# mega_pin_out_sides.net
KiCad netlist of a schematic drawn in EAGLE
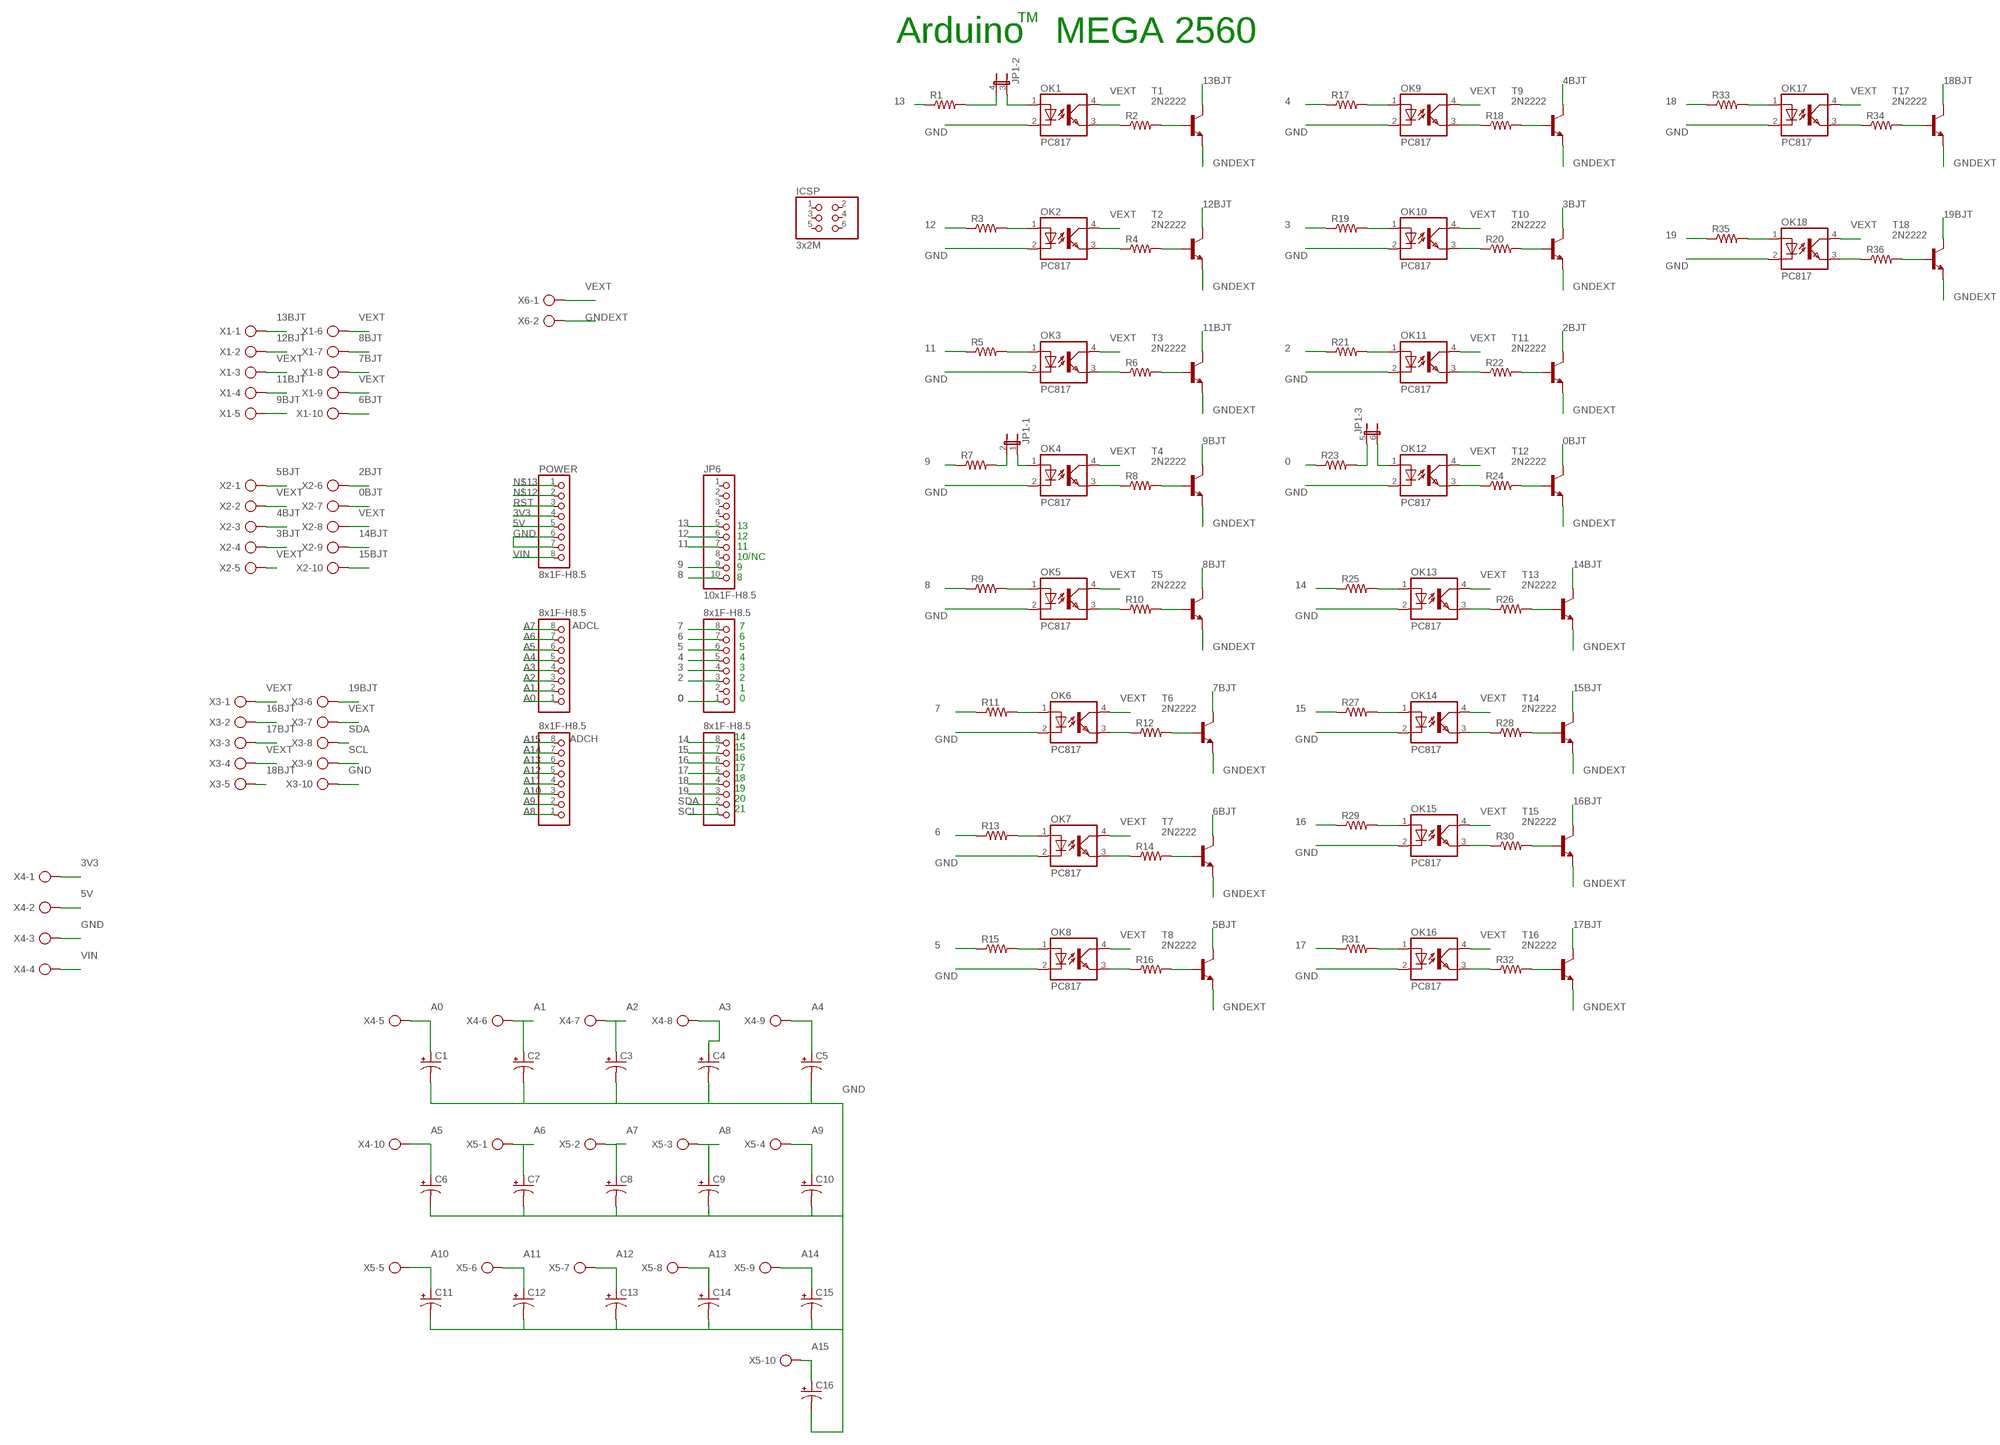
[diagram p0: schematic, sheet 1]

(export (version "E")
  (design (tool "Eeschema 10.0.6"))
  (components
    (comp (ref "ADCH")
      (value "8x1F-H8.5")
      (footprint "eagle-import:1X08")
      (libsource (lib "eagle-import") (part "PINHD-1X8"))
    )
    (comp (ref "ADCL")
      (value "8x1F-H8.5")
      (footprint "eagle-import:1X08")
      (libsource (lib "eagle-import") (part "PINHD-1X8"))
    )
    (comp (ref "C1")
      (value "CPOL-USE2-4")
      (footprint "eagle-import:E2-4")
      (libsource (lib "eagle-import") (part "CPOL-USE2-4"))
    )
    (comp (ref "C2")
      (value "CPOL-USE2-4")
      (footprint "eagle-import:E2-4")
      (libsource (lib "eagle-import") (part "CPOL-USE2-4"))
    )
    (comp (ref "C3")
      (value "CPOL-USE2-4")
      (footprint "eagle-import:E2-4")
      (libsource (lib "eagle-import") (part "CPOL-USE2-4"))
    )
    (comp (ref "C4")
      (value "CPOL-USE2-4")
      (footprint "eagle-import:E2-4")
      (libsource (lib "eagle-import") (part "CPOL-USE2-4"))
    )
    (comp (ref "C5")
      (value "CPOL-USE2-4")
      (footprint "eagle-import:E2-4")
      (libsource (lib "eagle-import") (part "CPOL-USE2-4"))
    )
    (comp (ref "C6")
      (value "CPOL-USE2-4")
      (footprint "eagle-import:E2-4")
      (libsource (lib "eagle-import") (part "CPOL-USE2-4"))
    )
    (comp (ref "C7")
      (value "CPOL-USE2-4")
      (footprint "eagle-import:E2-4")
      (libsource (lib "eagle-import") (part "CPOL-USE2-4"))
    )
    (comp (ref "C8")
      (value "CPOL-USE2-4")
      (footprint "eagle-import:E2-4")
      (libsource (lib "eagle-import") (part "CPOL-USE2-4"))
    )
    (comp (ref "C9")
      (value "CPOL-USE2-4")
      (footprint "eagle-import:E2-4")
      (libsource (lib "eagle-import") (part "CPOL-USE2-4"))
    )
    (comp (ref "C10")
      (value "CPOL-USE2-4")
      (footprint "eagle-import:E2-4")
      (libsource (lib "eagle-import") (part "CPOL-USE2-4"))
    )
    (comp (ref "C11")
      (value "CPOL-USE2-4")
      (footprint "eagle-import:E2-4")
      (libsource (lib "eagle-import") (part "CPOL-USE2-4"))
    )
    (comp (ref "C12")
      (value "CPOL-USE2-4")
      (footprint "eagle-import:E2-4")
      (libsource (lib "eagle-import") (part "CPOL-USE2-4"))
    )
    (comp (ref "C13")
      (value "CPOL-USE2-4")
      (footprint "eagle-import:E2-4")
      (libsource (lib "eagle-import") (part "CPOL-USE2-4"))
    )
    (comp (ref "C14")
      (value "CPOL-USE2-4")
      (footprint "eagle-import:E2-4")
      (libsource (lib "eagle-import") (part "CPOL-USE2-4"))
    )
    (comp (ref "C15")
      (value "CPOL-USE2-4")
      (footprint "eagle-import:E2-4")
      (libsource (lib "eagle-import") (part "CPOL-USE2-4"))
    )
    (comp (ref "C16")
      (value "CPOL-USE2-4")
      (footprint "eagle-import:E2-4")
      (libsource (lib "eagle-import") (part "CPOL-USE2-4"))
    )
    (comp (ref "COMMUNICATION")
      (value "8x1F-H8.5")
      (footprint "eagle-import:1X08")
      (libsource (lib "eagle-import") (part "PINHD-1X8"))
    )
    (comp (ref "ICSP")
      (value "3x2M")
      (footprint "eagle-import:2X03")
      (libsource (lib "eagle-import") (part "PINHD-2X3"))
    )
    (comp (ref "JP1")
      (value "JP3QE")
      (footprint "eagle-import:JP3Q")
      (libsource (lib "eagle-import") (part "JP3QE"))
    )
    (comp (ref "JP6")
      (value "10x1F-H8.5")
      (footprint "eagle-import:1X10")
      (libsource (lib "eagle-import") (part "PINHD-1X10_ARD"))
    )
    (comp (ref "OK1")
      (value "PC817")
      (footprint "eagle-import:DIL04")
      (fields (field (name "MPN") "PC817X4J000F"))
      (libsource (lib "eagle-import") (part "PC817"))
    )
    (comp (ref "OK2")
      (value "PC817")
      (footprint "eagle-import:DIL04")
      (fields (field (name "MPN") "PC817X4J000F"))
      (libsource (lib "eagle-import") (part "PC817"))
    )
    (comp (ref "OK3")
      (value "PC817")
      (footprint "eagle-import:DIL04")
      (fields (field (name "MPN") "PC817X4J000F"))
      (libsource (lib "eagle-import") (part "PC817"))
    )
    (comp (ref "OK4")
      (value "PC817")
      (footprint "eagle-import:DIL04")
      (fields (field (name "MPN") "PC817X4J000F"))
      (libsource (lib "eagle-import") (part "PC817"))
    )
    (comp (ref "OK5")
      (value "PC817")
      (footprint "eagle-import:DIL04")
      (fields (field (name "MPN") "PC817X4J000F"))
      (libsource (lib "eagle-import") (part "PC817"))
    )
    (comp (ref "OK6")
      (value "PC817")
      (footprint "eagle-import:DIL04")
      (fields (field (name "MPN") "PC817X4J000F"))
      (libsource (lib "eagle-import") (part "PC817"))
    )
    (comp (ref "OK7")
      (value "PC817")
      (footprint "eagle-import:DIL04")
      (fields (field (name "MPN") "PC817X4J000F"))
      (libsource (lib "eagle-import") (part "PC817"))
    )
    (comp (ref "OK8")
      (value "PC817")
      (footprint "eagle-import:DIL04")
      (fields (field (name "MPN") "PC817X4J000F"))
      (libsource (lib "eagle-import") (part "PC817"))
    )
    (comp (ref "OK9")
      (value "PC817")
      (footprint "eagle-import:DIL04")
      (fields (field (name "MPN") "PC817X4J000F"))
      (libsource (lib "eagle-import") (part "PC817"))
    )
    (comp (ref "OK10")
      (value "PC817")
      (footprint "eagle-import:DIL04")
      (fields (field (name "MPN") "PC817X4J000F"))
      (libsource (lib "eagle-import") (part "PC817"))
    )
    (comp (ref "OK11")
      (value "PC817")
      (footprint "eagle-import:DIL04")
      (fields (field (name "MPN") "PC817X4J000F"))
      (libsource (lib "eagle-import") (part "PC817"))
    )
    (comp (ref "OK12")
      (value "PC817")
      (footprint "eagle-import:DIL04")
      (fields (field (name "MPN") "PC817X4J000F"))
      (libsource (lib "eagle-import") (part "PC817"))
    )
    (comp (ref "OK13")
      (value "PC817")
      (footprint "eagle-import:DIL04")
      (fields (field (name "MPN") "PC817X4J000F"))
      (libsource (lib "eagle-import") (part "PC817"))
    )
    (comp (ref "OK14")
      (value "PC817")
      (footprint "eagle-import:DIL04")
      (fields (field (name "MPN") "PC817X4J000F"))
      (libsource (lib "eagle-import") (part "PC817"))
    )
    (comp (ref "OK15")
      (value "PC817")
      (footprint "eagle-import:DIL04")
      (fields (field (name "MPN") "PC817X4J000F"))
      (libsource (lib "eagle-import") (part "PC817"))
    )
    (comp (ref "OK16")
      (value "PC817")
      (footprint "eagle-import:DIL04")
      (fields (field (name "MPN") "PC817X4J000F"))
      (libsource (lib "eagle-import") (part "PC817"))
    )
    (comp (ref "OK17")
      (value "PC817")
      (footprint "eagle-import:DIL04")
      (fields (field (name "MPN") "PC817X4J000F"))
      (libsource (lib "eagle-import") (part "PC817"))
    )
    (comp (ref "OK18")
      (value "PC817")
      (footprint "eagle-import:DIL04")
      (fields (field (name "MPN") "PC817X4J000F"))
      (libsource (lib "eagle-import") (part "PC817"))
    )
    (comp (ref "POWER")
      (value "8x1F-H8.5")
      (footprint "eagle-import:1X08")
      (libsource (lib "eagle-import") (part "PINHD-1X8"))
    )
    (comp (ref "PWML")
      (value "8x1F-H8.5")
      (footprint "eagle-import:1X08")
      (libsource (lib "eagle-import") (part "PINHD-1X8"))
    )
    (comp (ref "R1")
      (value "R-US_M1206")
      (footprint "eagle-import:M1206")
      (libsource (lib "eagle-import") (part "R-US_M1206"))
    )
    (comp (ref "R2")
      (value "R-US_M1206")
      (footprint "eagle-import:M1206")
      (libsource (lib "eagle-import") (part "R-US_M1206"))
    )
    (comp (ref "R3")
      (value "R-US_M1206")
      (footprint "eagle-import:M1206")
      (libsource (lib "eagle-import") (part "R-US_M1206"))
    )
    (comp (ref "R4")
      (value "R-US_M1206")
      (footprint "eagle-import:M1206")
      (libsource (lib "eagle-import") (part "R-US_M1206"))
    )
    (comp (ref "R5")
      (value "R-US_M1206")
      (footprint "eagle-import:M1206")
      (libsource (lib "eagle-import") (part "R-US_M1206"))
    )
    (comp (ref "R6")
      (value "R-US_M1206")
      (footprint "eagle-import:M1206")
      (libsource (lib "eagle-import") (part "R-US_M1206"))
    )
    (comp (ref "R7")
      (value "R-US_M1206")
      (footprint "eagle-import:M1206")
      (libsource (lib "eagle-import") (part "R-US_M1206"))
    )
    (comp (ref "R8")
      (value "R-US_M1206")
      (footprint "eagle-import:M1206")
      (libsource (lib "eagle-import") (part "R-US_M1206"))
    )
    (comp (ref "R9")
      (value "R-US_M1206")
      (footprint "eagle-import:M1206")
      (libsource (lib "eagle-import") (part "R-US_M1206"))
    )
    (comp (ref "R10")
      (value "R-US_M1206")
      (footprint "eagle-import:M1206")
      (libsource (lib "eagle-import") (part "R-US_M1206"))
    )
    (comp (ref "R11")
      (value "R-US_M1206")
      (footprint "eagle-import:M1206")
      (libsource (lib "eagle-import") (part "R-US_M1206"))
    )
    (comp (ref "R12")
      (value "R-US_M1206")
      (footprint "eagle-import:M1206")
      (libsource (lib "eagle-import") (part "R-US_M1206"))
    )
    (comp (ref "R13")
      (value "R-US_M1206")
      (footprint "eagle-import:M1206")
      (libsource (lib "eagle-import") (part "R-US_M1206"))
    )
    (comp (ref "R14")
      (value "R-US_M1206")
      (footprint "eagle-import:M1206")
      (libsource (lib "eagle-import") (part "R-US_M1206"))
    )
    (comp (ref "R15")
      (value "R-US_M1206")
      (footprint "eagle-import:M1206")
      (libsource (lib "eagle-import") (part "R-US_M1206"))
    )
    (comp (ref "R16")
      (value "R-US_M1206")
      (footprint "eagle-import:M1206")
      (libsource (lib "eagle-import") (part "R-US_M1206"))
    )
    (comp (ref "R17")
      (value "R-US_M1206")
      (footprint "eagle-import:M1206")
      (libsource (lib "eagle-import") (part "R-US_M1206"))
    )
    (comp (ref "R18")
      (value "R-US_M1206")
      (footprint "eagle-import:M1206")
      (libsource (lib "eagle-import") (part "R-US_M1206"))
    )
    (comp (ref "R19")
      (value "R-US_M1206")
      (footprint "eagle-import:M1206")
      (libsource (lib "eagle-import") (part "R-US_M1206"))
    )
    (comp (ref "R20")
      (value "R-US_M1206")
      (footprint "eagle-import:M1206")
      (libsource (lib "eagle-import") (part "R-US_M1206"))
    )
    (comp (ref "R21")
      (value "R-US_M1206")
      (footprint "eagle-import:M1206")
      (libsource (lib "eagle-import") (part "R-US_M1206"))
    )
    (comp (ref "R22")
      (value "R-US_M1206")
      (footprint "eagle-import:M1206")
      (libsource (lib "eagle-import") (part "R-US_M1206"))
    )
    (comp (ref "R23")
      (value "R-US_M1206")
      (footprint "eagle-import:M1206")
      (libsource (lib "eagle-import") (part "R-US_M1206"))
    )
    (comp (ref "R24")
      (value "R-US_M1206")
      (footprint "eagle-import:M1206")
      (libsource (lib "eagle-import") (part "R-US_M1206"))
    )
    (comp (ref "R25")
      (value "R-US_M1206")
      (footprint "eagle-import:M1206")
      (libsource (lib "eagle-import") (part "R-US_M1206"))
    )
    (comp (ref "R26")
      (value "R-US_M1206")
      (footprint "eagle-import:M1206")
      (libsource (lib "eagle-import") (part "R-US_M1206"))
    )
    (comp (ref "R27")
      (value "R-US_M1206")
      (footprint "eagle-import:M1206")
      (libsource (lib "eagle-import") (part "R-US_M1206"))
    )
    (comp (ref "R28")
      (value "R-US_M1206")
      (footprint "eagle-import:M1206")
      (libsource (lib "eagle-import") (part "R-US_M1206"))
    )
    (comp (ref "R29")
      (value "R-US_M1206")
      (footprint "eagle-import:M1206")
      (libsource (lib "eagle-import") (part "R-US_M1206"))
    )
    (comp (ref "R30")
      (value "R-US_M1206")
      (footprint "eagle-import:M1206")
      (libsource (lib "eagle-import") (part "R-US_M1206"))
    )
    (comp (ref "R31")
      (value "R-US_M1206")
      (footprint "eagle-import:M1206")
      (libsource (lib "eagle-import") (part "R-US_M1206"))
    )
    (comp (ref "R32")
      (value "R-US_M1206")
      (footprint "eagle-import:M1206")
      (libsource (lib "eagle-import") (part "R-US_M1206"))
    )
    (comp (ref "R33")
      (value "R-US_M1206")
      (footprint "eagle-import:M1206")
      (libsource (lib "eagle-import") (part "R-US_M1206"))
    )
    (comp (ref "R34")
      (value "R-US_M1206")
      (footprint "eagle-import:M1206")
      (libsource (lib "eagle-import") (part "R-US_M1206"))
    )
    (comp (ref "R35")
      (value "R-US_M1206")
      (footprint "eagle-import:M1206")
      (libsource (lib "eagle-import") (part "R-US_M1206"))
    )
    (comp (ref "R36")
      (value "R-US_M1206")
      (footprint "eagle-import:M1206")
      (libsource (lib "eagle-import") (part "R-US_M1206"))
    )
    (comp (ref "T1")
      (value "2N2222")
      (footprint "eagle-import:TO18")
      (libsource (lib "eagle-import") (part "2N2222"))
    )
    (comp (ref "T2")
      (value "2N2222")
      (footprint "eagle-import:TO18")
      (libsource (lib "eagle-import") (part "2N2222"))
    )
    (comp (ref "T3")
      (value "2N2222")
      (footprint "eagle-import:TO18")
      (libsource (lib "eagle-import") (part "2N2222"))
    )
    (comp (ref "T4")
      (value "2N2222")
      (footprint "eagle-import:TO18")
      (libsource (lib "eagle-import") (part "2N2222"))
    )
    (comp (ref "T5")
      (value "2N2222")
      (footprint "eagle-import:TO18")
      (libsource (lib "eagle-import") (part "2N2222"))
    )
    (comp (ref "T6")
      (value "2N2222")
      (footprint "eagle-import:TO18")
      (libsource (lib "eagle-import") (part "2N2222"))
    )
    (comp (ref "T7")
      (value "2N2222")
      (footprint "eagle-import:TO18")
      (libsource (lib "eagle-import") (part "2N2222"))
    )
    (comp (ref "T8")
      (value "2N2222")
      (footprint "eagle-import:TO18")
      (libsource (lib "eagle-import") (part "2N2222"))
    )
    (comp (ref "T9")
      (value "2N2222")
      (footprint "eagle-import:TO18")
      (libsource (lib "eagle-import") (part "2N2222"))
    )
    (comp (ref "T10")
      (value "2N2222")
      (footprint "eagle-import:TO18")
      (libsource (lib "eagle-import") (part "2N2222"))
    )
    (comp (ref "T11")
      (value "2N2222")
      (footprint "eagle-import:TO18")
      (libsource (lib "eagle-import") (part "2N2222"))
    )
    (comp (ref "T12")
      (value "2N2222")
      (footprint "eagle-import:TO18")
      (libsource (lib "eagle-import") (part "2N2222"))
    )
    (comp (ref "T13")
      (value "2N2222")
      (footprint "eagle-import:TO18")
      (libsource (lib "eagle-import") (part "2N2222"))
    )
    (comp (ref "T14")
      (value "2N2222")
      (footprint "eagle-import:TO18")
      (libsource (lib "eagle-import") (part "2N2222"))
    )
    (comp (ref "T15")
      (value "2N2222")
      (footprint "eagle-import:TO18")
      (libsource (lib "eagle-import") (part "2N2222"))
    )
    (comp (ref "T16")
      (value "2N2222")
      (footprint "eagle-import:TO18")
      (libsource (lib "eagle-import") (part "2N2222"))
    )
    (comp (ref "T17")
      (value "2N2222")
      (footprint "eagle-import:TO18")
      (libsource (lib "eagle-import") (part "2N2222"))
    )
    (comp (ref "T18")
      (value "2N2222")
      (footprint "eagle-import:TO18")
      (libsource (lib "eagle-import") (part "2N2222"))
    )
    (comp (ref "X1")
      (value "AK500/10")
      (footprint "eagle-import:AK500_10")
      (libsource (lib "eagle-import") (part "AK500/10"))
    )
    (comp (ref "X2")
      (value "AK500/10")
      (footprint "eagle-import:AK500_10")
      (libsource (lib "eagle-import") (part "AK500/10"))
    )
    (comp (ref "X3")
      (value "AK500/10")
      (footprint "eagle-import:AK500_10")
      (libsource (lib "eagle-import") (part "AK500/10"))
    )
    (comp (ref "X4")
      (value "AK500/10")
      (footprint "eagle-import:AK500_10")
      (libsource (lib "eagle-import") (part "AK500/10"))
    )
    (comp (ref "X5")
      (value "AK500/10")
      (footprint "eagle-import:AK500_10")
      (libsource (lib "eagle-import") (part "AK500/10"))
    )
    (comp (ref "X6")
      (value "AK500/2")
      (footprint "eagle-import:AK500_2")
      (libsource (lib "eagle-import") (part "AK500/2"))
    )
  )
  (nets
    (net (code "1") (name "/0") (class "Default")
      (node (ref "PWML") (pin "1") (pinfunction "1_1") (pintype "passive"))
      (node (ref "R23") (pin "1") (pinfunction "1_1") (pintype "passive"))
    )
    (net (code "2") (name "/0BJT") (class "Default")
      (node (ref "T12") (pin "3") (pinfunction "C_3") (pintype "passive"))
      (node (ref "X2") (pin "7") (pinfunction "KL_7") (pintype "passive"))
    )
    (net (code "3") (name "/2") (class "Default")
      (node (ref "PWML") (pin "3") (pinfunction "3_3") (pintype "passive"))
      (node (ref "R21") (pin "1") (pinfunction "1_1") (pintype "passive"))
    )
    (net (code "4") (name "/2BJT") (class "Default")
      (node (ref "T11") (pin "3") (pinfunction "C_3") (pintype "passive"))
      (node (ref "X2") (pin "6") (pinfunction "KL_6") (pintype "passive"))
    )
    (net (code "5") (name "/3") (class "Default")
      (node (ref "PWML") (pin "4") (pinfunction "4_4") (pintype "passive"))
      (node (ref "R19") (pin "1") (pinfunction "1_1") (pintype "passive"))
    )
    (net (code "6") (name "/3BJT") (class "Default")
      (node (ref "T10") (pin "3") (pinfunction "C_3") (pintype "passive"))
      (node (ref "X2") (pin "4") (pinfunction "KL_4") (pintype "passive"))
    )
    (net (code "7") (name "/3V3") (class "Default")
      (node (ref "POWER") (pin "4") (pinfunction "4_4") (pintype "passive"))
      (node (ref "X4") (pin "1") (pinfunction "KL_1") (pintype "passive"))
    )
    (net (code "8") (name "/4") (class "Default")
      (node (ref "PWML") (pin "5") (pinfunction "5_5") (pintype "passive"))
      (node (ref "R17") (pin "1") (pinfunction "1_1") (pintype "passive"))
    )
    (net (code "9") (name "/4BJT") (class "Default")
      (node (ref "T9") (pin "3") (pinfunction "C_3") (pintype "passive"))
      (node (ref "X2") (pin "3") (pinfunction "KL_3") (pintype "passive"))
    )
    (net (code "10") (name "/5") (class "Default")
      (node (ref "PWML") (pin "6") (pinfunction "6_6") (pintype "passive"))
      (node (ref "R15") (pin "1") (pinfunction "1_1") (pintype "passive"))
    )
    (net (code "11") (name "/5BJT") (class "Default")
      (node (ref "T8") (pin "3") (pinfunction "C_3") (pintype "passive"))
      (node (ref "X2") (pin "1") (pinfunction "KL_1") (pintype "passive"))
    )
    (net (code "12") (name "/5V") (class "Default")
      (node (ref "POWER") (pin "5") (pinfunction "5_5") (pintype "passive"))
      (node (ref "X4") (pin "2") (pinfunction "KL_2") (pintype "passive"))
    )
    (net (code "13") (name "/6") (class "Default")
      (node (ref "PWML") (pin "7") (pinfunction "7_7") (pintype "passive"))
      (node (ref "R13") (pin "1") (pinfunction "1_1") (pintype "passive"))
    )
    (net (code "14") (name "/6BJT") (class "Default")
      (node (ref "T7") (pin "3") (pinfunction "C_3") (pintype "passive"))
      (node (ref "X1") (pin "10") (pinfunction "KL_10") (pintype "passive"))
    )
    (net (code "15") (name "/7") (class "Default")
      (node (ref "PWML") (pin "8") (pinfunction "8_8") (pintype "passive"))
      (node (ref "R11") (pin "1") (pinfunction "1_1") (pintype "passive"))
    )
    (net (code "16") (name "/7BJT") (class "Default")
      (node (ref "T6") (pin "3") (pinfunction "C_3") (pintype "passive"))
      (node (ref "X1") (pin "8") (pinfunction "KL_8") (pintype "passive"))
    )
    (net (code "17") (name "/8") (class "Default")
      (node (ref "JP6") (pin "10") (pinfunction "10_10") (pintype "passive"))
      (node (ref "R9") (pin "1") (pinfunction "1_1") (pintype "passive"))
    )
    (net (code "18") (name "/8BJT") (class "Default")
      (node (ref "T5") (pin "3") (pinfunction "C_3") (pintype "passive"))
      (node (ref "X1") (pin "7") (pinfunction "KL_7") (pintype "passive"))
    )
    (net (code "19") (name "/9") (class "Default")
      (node (ref "JP6") (pin "9") (pinfunction "9_9") (pintype "passive"))
      (node (ref "R7") (pin "1") (pinfunction "1_1") (pintype "passive"))
    )
    (net (code "20") (name "/9BJT") (class "Default")
      (node (ref "T4") (pin "3") (pinfunction "C_3") (pintype "passive"))
      (node (ref "X1") (pin "5") (pinfunction "KL_5") (pintype "passive"))
    )
    (net (code "21") (name "/11") (class "Default")
      (node (ref "JP6") (pin "7") (pinfunction "7_7") (pintype "passive"))
      (node (ref "R5") (pin "1") (pinfunction "1_1") (pintype "passive"))
    )
    (net (code "22") (name "/11BJT") (class "Default")
      (node (ref "T3") (pin "3") (pinfunction "C_3") (pintype "passive"))
      (node (ref "X1") (pin "4") (pinfunction "KL_4") (pintype "passive"))
    )
    (net (code "23") (name "/12") (class "Default")
      (node (ref "JP6") (pin "6") (pinfunction "6_6") (pintype "passive"))
      (node (ref "R3") (pin "1") (pinfunction "1_1") (pintype "passive"))
    )
    (net (code "24") (name "/12BJT") (class "Default")
      (node (ref "T2") (pin "3") (pinfunction "C_3") (pintype "passive"))
      (node (ref "X1") (pin "2") (pinfunction "KL_2") (pintype "passive"))
    )
    (net (code "25") (name "/13") (class "Default")
      (node (ref "JP6") (pin "5") (pinfunction "5_5") (pintype "passive"))
      (node (ref "R1") (pin "1") (pinfunction "1_1") (pintype "passive"))
    )
    (net (code "26") (name "/13BJT") (class "Default")
      (node (ref "T1") (pin "3") (pinfunction "C_3") (pintype "passive"))
      (node (ref "X1") (pin "1") (pinfunction "KL_1") (pintype "passive"))
    )
    (net (code "27") (name "/14") (class "Default")
      (node (ref "COMMUNICATION") (pin "8") (pinfunction "8_8") (pintype "passive"))
      (node (ref "R25") (pin "1") (pinfunction "1_1") (pintype "passive"))
    )
    (net (code "28") (name "/14BJT") (class "Default")
      (node (ref "T13") (pin "3") (pinfunction "C_3") (pintype "passive"))
      (node (ref "X2") (pin "9") (pinfunction "KL_9") (pintype "passive"))
    )
    (net (code "29") (name "/15") (class "Default")
      (node (ref "COMMUNICATION") (pin "7") (pinfunction "7_7") (pintype "passive"))
      (node (ref "R27") (pin "1") (pinfunction "1_1") (pintype "passive"))
    )
    (net (code "30") (name "/15BJT") (class "Default")
      (node (ref "T14") (pin "3") (pinfunction "C_3") (pintype "passive"))
      (node (ref "X2") (pin "10") (pinfunction "KL_10") (pintype "passive"))
    )
    (net (code "31") (name "/16") (class "Default")
      (node (ref "COMMUNICATION") (pin "6") (pinfunction "6_6") (pintype "passive"))
      (node (ref "R29") (pin "1") (pinfunction "1_1") (pintype "passive"))
    )
    (net (code "32") (name "/16BJT") (class "Default")
      (node (ref "T15") (pin "3") (pinfunction "C_3") (pintype "passive"))
      (node (ref "X3") (pin "2") (pinfunction "KL_2") (pintype "passive"))
    )
    (net (code "33") (name "/17") (class "Default")
      (node (ref "COMMUNICATION") (pin "5") (pinfunction "5_5") (pintype "passive"))
      (node (ref "R31") (pin "1") (pinfunction "1_1") (pintype "passive"))
    )
    (net (code "34") (name "/17BJT") (class "Default")
      (node (ref "T16") (pin "3") (pinfunction "C_3") (pintype "passive"))
      (node (ref "X3") (pin "3") (pinfunction "KL_3") (pintype "passive"))
    )
    (net (code "35") (name "/18") (class "Default")
      (node (ref "COMMUNICATION") (pin "4") (pinfunction "4_4") (pintype "passive"))
      (node (ref "R33") (pin "1") (pinfunction "1_1") (pintype "passive"))
    )
    (net (code "36") (name "/18BJT") (class "Default")
      (node (ref "T17") (pin "3") (pinfunction "C_3") (pintype "passive"))
      (node (ref "X3") (pin "5") (pinfunction "KL_5") (pintype "passive"))
    )
    (net (code "37") (name "/19") (class "Default")
      (node (ref "COMMUNICATION") (pin "3") (pinfunction "3_3") (pintype "passive"))
      (node (ref "R35") (pin "1") (pinfunction "1_1") (pintype "passive"))
    )
    (net (code "38") (name "/19BJT") (class "Default")
      (node (ref "T18") (pin "3") (pinfunction "C_3") (pintype "passive"))
      (node (ref "X3") (pin "6") (pinfunction "KL_6") (pintype "passive"))
    )
    (net (code "39") (name "/A0") (class "Default")
      (node (ref "ADCL") (pin "1") (pinfunction "1_1") (pintype "passive"))
      (node (ref "C1") (pin "+") (pinfunction "+_+") (pintype "passive"))
      (node (ref "X4") (pin "5") (pinfunction "KL_5") (pintype "passive"))
    )
    (net (code "40") (name "/A1") (class "Default")
      (node (ref "ADCL") (pin "2") (pinfunction "2_2") (pintype "passive"))
      (node (ref "C2") (pin "+") (pinfunction "+_+") (pintype "passive"))
      (node (ref "X4") (pin "6") (pinfunction "KL_6") (pintype "passive"))
    )
    (net (code "41") (name "/A2") (class "Default")
      (node (ref "ADCL") (pin "3") (pinfunction "3_3") (pintype "passive"))
      (node (ref "C3") (pin "+") (pinfunction "+_+") (pintype "passive"))
      (node (ref "X4") (pin "7") (pinfunction "KL_7") (pintype "passive"))
    )
    (net (code "42") (name "/A3") (class "Default")
      (node (ref "ADCL") (pin "4") (pinfunction "4_4") (pintype "passive"))
      (node (ref "C4") (pin "+") (pinfunction "+_+") (pintype "passive"))
      (node (ref "X4") (pin "8") (pinfunction "KL_8") (pintype "passive"))
    )
    (net (code "43") (name "/A4") (class "Default")
      (node (ref "ADCL") (pin "5") (pinfunction "5_5") (pintype "passive"))
      (node (ref "C5") (pin "+") (pinfunction "+_+") (pintype "passive"))
      (node (ref "X4") (pin "9") (pinfunction "KL_9") (pintype "passive"))
    )
    (net (code "44") (name "/A5") (class "Default")
      (node (ref "ADCL") (pin "6") (pinfunction "6_6") (pintype "passive"))
      (node (ref "C6") (pin "+") (pinfunction "+_+") (pintype "passive"))
      (node (ref "X4") (pin "10") (pinfunction "KL_10") (pintype "passive"))
    )
    (net (code "45") (name "/A6") (class "Default")
      (node (ref "ADCL") (pin "7") (pinfunction "7_7") (pintype "passive"))
      (node (ref "C7") (pin "+") (pinfunction "+_+") (pintype "passive"))
      (node (ref "X5") (pin "1") (pinfunction "KL_1") (pintype "passive"))
    )
    (net (code "46") (name "/A7") (class "Default")
      (node (ref "ADCL") (pin "8") (pinfunction "8_8") (pintype "passive"))
      (node (ref "C8") (pin "+") (pinfunction "+_+") (pintype "passive"))
      (node (ref "X5") (pin "2") (pinfunction "KL_2") (pintype "passive"))
    )
    (net (code "47") (name "/A8") (class "Default")
      (node (ref "ADCH") (pin "1") (pinfunction "1_1") (pintype "passive"))
      (node (ref "C9") (pin "+") (pinfunction "+_+") (pintype "passive"))
      (node (ref "X5") (pin "3") (pinfunction "KL_3") (pintype "passive"))
    )
    (net (code "48") (name "/A9") (class "Default")
      (node (ref "ADCH") (pin "2") (pinfunction "2_2") (pintype "passive"))
      (node (ref "C10") (pin "+") (pinfunction "+_+") (pintype "passive"))
      (node (ref "X5") (pin "4") (pinfunction "KL_4") (pintype "passive"))
    )
    (net (code "49") (name "/A10") (class "Default")
      (node (ref "ADCH") (pin "3") (pinfunction "3_3") (pintype "passive"))
      (node (ref "C11") (pin "+") (pinfunction "+_+") (pintype "passive"))
      (node (ref "X5") (pin "5") (pinfunction "KL_5") (pintype "passive"))
    )
    (net (code "50") (name "/A11") (class "Default")
      (node (ref "ADCH") (pin "4") (pinfunction "4_4") (pintype "passive"))
      (node (ref "C12") (pin "+") (pinfunction "+_+") (pintype "passive"))
      (node (ref "X5") (pin "6") (pinfunction "KL_6") (pintype "passive"))
    )
    (net (code "51") (name "/A12") (class "Default")
      (node (ref "ADCH") (pin "5") (pinfunction "5_5") (pintype "passive"))
      (node (ref "C13") (pin "+") (pinfunction "+_+") (pintype "passive"))
      (node (ref "X5") (pin "7") (pinfunction "KL_7") (pintype "passive"))
    )
    (net (code "52") (name "/A13") (class "Default")
      (node (ref "ADCH") (pin "6") (pinfunction "6_6") (pintype "passive"))
      (node (ref "C14") (pin "+") (pinfunction "+_+") (pintype "passive"))
      (node (ref "X5") (pin "8") (pinfunction "KL_8") (pintype "passive"))
    )
    (net (code "53") (name "/A14") (class "Default")
      (node (ref "ADCH") (pin "7") (pinfunction "7_7") (pintype "passive"))
      (node (ref "C15") (pin "+") (pinfunction "+_+") (pintype "passive"))
      (node (ref "X5") (pin "9") (pinfunction "KL_9") (pintype "passive"))
    )
    (net (code "54") (name "/A15") (class "Default")
      (node (ref "ADCH") (pin "8") (pinfunction "8_8") (pintype "passive"))
      (node (ref "C16") (pin "+") (pinfunction "+_+") (pintype "passive"))
      (node (ref "X5") (pin "10") (pinfunction "KL_10") (pintype "passive"))
    )
    (net (code "55") (name "/GND") (class "Default")
      (node (ref "C1") (pin "-") (pinfunction "-_-") (pintype "passive"))
      (node (ref "C10") (pin "-") (pinfunction "-_-") (pintype "passive"))
      (node (ref "C11") (pin "-") (pinfunction "-_-") (pintype "passive"))
      (node (ref "C12") (pin "-") (pinfunction "-_-") (pintype "passive"))
      (node (ref "C13") (pin "-") (pinfunction "-_-") (pintype "passive"))
      (node (ref "C14") (pin "-") (pinfunction "-_-") (pintype "passive"))
      (node (ref "C15") (pin "-") (pinfunction "-_-") (pintype "passive"))
      (node (ref "C16") (pin "-") (pinfunction "-_-") (pintype "passive"))
      (node (ref "C2") (pin "-") (pinfunction "-_-") (pintype "passive"))
      (node (ref "C3") (pin "-") (pinfunction "-_-") (pintype "passive"))
      (node (ref "C4") (pin "-") (pinfunction "-_-") (pintype "passive"))
      (node (ref "C5") (pin "-") (pinfunction "-_-") (pintype "passive"))
      (node (ref "C6") (pin "-") (pinfunction "-_-") (pintype "passive"))
      (node (ref "C7") (pin "-") (pinfunction "-_-") (pintype "passive"))
      (node (ref "C8") (pin "-") (pinfunction "-_-") (pintype "passive"))
      (node (ref "C9") (pin "-") (pinfunction "-_-") (pintype "passive"))
      (node (ref "OK1") (pin "2") (pinfunction "C_2") (pintype "passive"))
      (node (ref "OK10") (pin "2") (pinfunction "C_2") (pintype "passive"))
      (node (ref "OK11") (pin "2") (pinfunction "C_2") (pintype "passive"))
      (node (ref "OK12") (pin "2") (pinfunction "C_2") (pintype "passive"))
      (node (ref "OK13") (pin "2") (pinfunction "C_2") (pintype "passive"))
      (node (ref "OK14") (pin "2") (pinfunction "C_2") (pintype "passive"))
      (node (ref "OK15") (pin "2") (pinfunction "C_2") (pintype "passive"))
      (node (ref "OK16") (pin "2") (pinfunction "C_2") (pintype "passive"))
      (node (ref "OK17") (pin "2") (pinfunction "C_2") (pintype "passive"))
      (node (ref "OK18") (pin "2") (pinfunction "C_2") (pintype "passive"))
      (node (ref "OK2") (pin "2") (pinfunction "C_2") (pintype "passive"))
      (node (ref "OK3") (pin "2") (pinfunction "C_2") (pintype "passive"))
      (node (ref "OK4") (pin "2") (pinfunction "C_2") (pintype "passive"))
      (node (ref "OK5") (pin "2") (pinfunction "C_2") (pintype "passive"))
      (node (ref "OK6") (pin "2") (pinfunction "C_2") (pintype "passive"))
      (node (ref "OK7") (pin "2") (pinfunction "C_2") (pintype "passive"))
      (node (ref "OK8") (pin "2") (pinfunction "C_2") (pintype "passive"))
      (node (ref "OK9") (pin "2") (pinfunction "C_2") (pintype "passive"))
      (node (ref "POWER") (pin "6") (pinfunction "6_6") (pintype "passive"))
      (node (ref "POWER") (pin "7") (pinfunction "7_7") (pintype "passive"))
      (node (ref "X3") (pin "10") (pinfunction "KL_10") (pintype "passive"))
      (node (ref "X4") (pin "3") (pinfunction "KL_3") (pintype "passive"))
    )
    (net (code "56") (name "/GNDEXT") (class "Default")
      (node (ref "T1") (pin "1") (pinfunction "E_1") (pintype "passive"))
      (node (ref "T10") (pin "1") (pinfunction "E_1") (pintype "passive"))
      (node (ref "T11") (pin "1") (pinfunction "E_1") (pintype "passive"))
      (node (ref "T12") (pin "1") (pinfunction "E_1") (pintype "passive"))
      (node (ref "T13") (pin "1") (pinfunction "E_1") (pintype "passive"))
      (node (ref "T14") (pin "1") (pinfunction "E_1") (pintype "passive"))
      (node (ref "T15") (pin "1") (pinfunction "E_1") (pintype "passive"))
      (node (ref "T16") (pin "1") (pinfunction "E_1") (pintype "passive"))
      (node (ref "T17") (pin "1") (pinfunction "E_1") (pintype "passive"))
      (node (ref "T18") (pin "1") (pinfunction "E_1") (pintype "passive"))
      (node (ref "T2") (pin "1") (pinfunction "E_1") (pintype "passive"))
      (node (ref "T3") (pin "1") (pinfunction "E_1") (pintype "passive"))
      (node (ref "T4") (pin "1") (pinfunction "E_1") (pintype "passive"))
      (node (ref "T5") (pin "1") (pinfunction "E_1") (pintype "passive"))
      (node (ref "T6") (pin "1") (pinfunction "E_1") (pintype "passive"))
      (node (ref "T7") (pin "1") (pinfunction "E_1") (pintype "passive"))
      (node (ref "T8") (pin "1") (pinfunction "E_1") (pintype "passive"))
      (node (ref "T9") (pin "1") (pinfunction "E_1") (pintype "passive"))
      (node (ref "X6") (pin "2") (pinfunction "KL_2") (pintype "passive"))
    )
    (net (code "57") (name "/N$12") (class "Default")
      (node (ref "POWER") (pin "2") (pinfunction "2_2") (pintype "passive"))
    )
    (net (code "58") (name "/N$13") (class "Default")
      (node (ref "POWER") (pin "1") (pinfunction "1_1") (pintype "passive"))
    )
    (net (code "59") (name "/RST") (class "Default")
      (node (ref "POWER") (pin "3") (pinfunction "3_3") (pintype "passive"))
    )
    (net (code "60") (name "/SCL") (class "Default")
      (node (ref "COMMUNICATION") (pin "1") (pinfunction "1_1") (pintype "passive"))
      (node (ref "X3") (pin "9") (pinfunction "KL_9") (pintype "passive"))
    )
    (net (code "61") (name "/SDA") (class "Default")
      (node (ref "COMMUNICATION") (pin "2") (pinfunction "2_2") (pintype "passive"))
      (node (ref "X3") (pin "8") (pinfunction "KL_8") (pintype "passive"))
    )
    (net (code "62") (name "/VEXT") (class "Default")
      (node (ref "OK1") (pin "4") (pinfunction "COL_4") (pintype "passive"))
      (node (ref "OK10") (pin "4") (pinfunction "COL_4") (pintype "passive"))
      (node (ref "OK11") (pin "4") (pinfunction "COL_4") (pintype "passive"))
      (node (ref "OK12") (pin "4") (pinfunction "COL_4") (pintype "passive"))
      (node (ref "OK13") (pin "4") (pinfunction "COL_4") (pintype "passive"))
      (node (ref "OK14") (pin "4") (pinfunction "COL_4") (pintype "passive"))
      (node (ref "OK15") (pin "4") (pinfunction "COL_4") (pintype "passive"))
      (node (ref "OK16") (pin "4") (pinfunction "COL_4") (pintype "passive"))
      (node (ref "OK17") (pin "4") (pinfunction "COL_4") (pintype "passive"))
      (node (ref "OK18") (pin "4") (pinfunction "COL_4") (pintype "passive"))
      (node (ref "OK2") (pin "4") (pinfunction "COL_4") (pintype "passive"))
      (node (ref "OK3") (pin "4") (pinfunction "COL_4") (pintype "passive"))
      (node (ref "OK4") (pin "4") (pinfunction "COL_4") (pintype "passive"))
      (node (ref "OK5") (pin "4") (pinfunction "COL_4") (pintype "passive"))
      (node (ref "OK6") (pin "4") (pinfunction "COL_4") (pintype "passive"))
      (node (ref "OK7") (pin "4") (pinfunction "COL_4") (pintype "passive"))
      (node (ref "OK8") (pin "4") (pinfunction "COL_4") (pintype "passive"))
      (node (ref "OK9") (pin "4") (pinfunction "COL_4") (pintype "passive"))
      (node (ref "X1") (pin "3") (pinfunction "KL_3") (pintype "passive"))
      (node (ref "X1") (pin "6") (pinfunction "KL_6") (pintype "passive"))
      (node (ref "X1") (pin "9") (pinfunction "KL_9") (pintype "passive"))
      (node (ref "X2") (pin "2") (pinfunction "KL_2") (pintype "passive"))
      (node (ref "X2") (pin "5") (pinfunction "KL_5") (pintype "passive"))
      (node (ref "X2") (pin "8") (pinfunction "KL_8") (pintype "passive"))
      (node (ref "X3") (pin "1") (pinfunction "KL_1") (pintype "passive"))
      (node (ref "X3") (pin "4") (pinfunction "KL_4") (pintype "passive"))
      (node (ref "X3") (pin "7") (pinfunction "KL_7") (pintype "passive"))
      (node (ref "X6") (pin "1") (pinfunction "KL_1") (pintype "passive"))
    )
    (net (code "63") (name "/VIN") (class "Default")
      (node (ref "POWER") (pin "8") (pinfunction "8_8") (pintype "passive"))
      (node (ref "X4") (pin "4") (pinfunction "KL_4") (pintype "passive"))
    )
    (net (code "64") (name "Net-(JP1-Pad2)") (class "Default")
      (node (ref "JP1") (pin "2") (pinfunction "2_2") (pintype "passive"))
      (node (ref "R7") (pin "2") (pinfunction "2_2") (pintype "passive"))
    )
    (net (code "65") (name "Net-(JP1B-1)") (class "Default")
      (node (ref "JP1") (pin "3") (pinfunction "1_3") (pintype "passive"))
      (node (ref "OK1") (pin "1") (pinfunction "A_1") (pintype "passive"))
    )
    (net (code "66") (name "Net-(JP1B-2)") (class "Default")
      (node (ref "JP1") (pin "4") (pinfunction "2_4") (pintype "passive"))
      (node (ref "R1") (pin "2") (pinfunction "2_2") (pintype "passive"))
    )
    (net (code "67") (name "Net-(JP1C-1)") (class "Default")
      (node (ref "JP1") (pin "5") (pinfunction "1_5") (pintype "passive"))
      (node (ref "R23") (pin "2") (pinfunction "2_2") (pintype "passive"))
    )
    (net (code "68") (name "Net-(JP1C-2)") (class "Default")
      (node (ref "JP1") (pin "6") (pinfunction "2_6") (pintype "passive"))
      (node (ref "OK12") (pin "1") (pinfunction "A_1") (pintype "passive"))
    )
    (net (code "69") (name "Net-(OK1-EMIT)") (class "Default")
      (node (ref "OK1") (pin "3") (pinfunction "EMIT_3") (pintype "passive"))
      (node (ref "R2") (pin "1") (pinfunction "1_1") (pintype "passive"))
    )
    (net (code "70") (name "Net-(OK2-A)") (class "Default")
      (node (ref "OK2") (pin "1") (pinfunction "A_1") (pintype "passive"))
      (node (ref "R3") (pin "2") (pinfunction "2_2") (pintype "passive"))
    )
    (net (code "71") (name "Net-(OK2-EMIT)") (class "Default")
      (node (ref "OK2") (pin "3") (pinfunction "EMIT_3") (pintype "passive"))
      (node (ref "R4") (pin "1") (pinfunction "1_1") (pintype "passive"))
    )
    (net (code "72") (name "Net-(OK3-A)") (class "Default")
      (node (ref "OK3") (pin "1") (pinfunction "A_1") (pintype "passive"))
      (node (ref "R5") (pin "2") (pinfunction "2_2") (pintype "passive"))
    )
    (net (code "73") (name "Net-(OK3-EMIT)") (class "Default")
      (node (ref "OK3") (pin "3") (pinfunction "EMIT_3") (pintype "passive"))
      (node (ref "R6") (pin "1") (pinfunction "1_1") (pintype "passive"))
    )
    (net (code "74") (name "Net-(OK4-A)") (class "Default")
      (node (ref "JP1") (pin "1") (pinfunction "1_1") (pintype "passive"))
      (node (ref "OK4") (pin "1") (pinfunction "A_1") (pintype "passive"))
    )
    (net (code "75") (name "Net-(OK4-EMIT)") (class "Default")
      (node (ref "OK4") (pin "3") (pinfunction "EMIT_3") (pintype "passive"))
      (node (ref "R8") (pin "1") (pinfunction "1_1") (pintype "passive"))
    )
    (net (code "76") (name "Net-(OK5-A)") (class "Default")
      (node (ref "OK5") (pin "1") (pinfunction "A_1") (pintype "passive"))
      (node (ref "R9") (pin "2") (pinfunction "2_2") (pintype "passive"))
    )
    (net (code "77") (name "Net-(OK5-EMIT)") (class "Default")
      (node (ref "OK5") (pin "3") (pinfunction "EMIT_3") (pintype "passive"))
      (node (ref "R10") (pin "1") (pinfunction "1_1") (pintype "passive"))
    )
    (net (code "78") (name "Net-(OK6-A)") (class "Default")
      (node (ref "OK6") (pin "1") (pinfunction "A_1") (pintype "passive"))
      (node (ref "R11") (pin "2") (pinfunction "2_2") (pintype "passive"))
    )
    (net (code "79") (name "Net-(OK6-EMIT)") (class "Default")
      (node (ref "OK6") (pin "3") (pinfunction "EMIT_3") (pintype "passive"))
      (node (ref "R12") (pin "1") (pinfunction "1_1") (pintype "passive"))
    )
    (net (code "80") (name "Net-(OK7-A)") (class "Default")
      (node (ref "OK7") (pin "1") (pinfunction "A_1") (pintype "passive"))
      (node (ref "R13") (pin "2") (pinfunction "2_2") (pintype "passive"))
    )
    (net (code "81") (name "Net-(OK7-EMIT)") (class "Default")
      (node (ref "OK7") (pin "3") (pinfunction "EMIT_3") (pintype "passive"))
      (node (ref "R14") (pin "1") (pinfunction "1_1") (pintype "passive"))
    )
    (net (code "82") (name "Net-(OK8-A)") (class "Default")
      (node (ref "OK8") (pin "1") (pinfunction "A_1") (pintype "passive"))
      (node (ref "R15") (pin "2") (pinfunction "2_2") (pintype "passive"))
    )
    (net (code "83") (name "Net-(OK8-EMIT)") (class "Default")
      (node (ref "OK8") (pin "3") (pinfunction "EMIT_3") (pintype "passive"))
      (node (ref "R16") (pin "1") (pinfunction "1_1") (pintype "passive"))
    )
    (net (code "84") (name "Net-(OK9-A)") (class "Default")
      (node (ref "OK9") (pin "1") (pinfunction "A_1") (pintype "passive"))
      (node (ref "R17") (pin "2") (pinfunction "2_2") (pintype "passive"))
    )
    (net (code "85") (name "Net-(OK9-EMIT)") (class "Default")
      (node (ref "OK9") (pin "3") (pinfunction "EMIT_3") (pintype "passive"))
      (node (ref "R18") (pin "1") (pinfunction "1_1") (pintype "passive"))
    )
    (net (code "86") (name "Net-(OK10-A)") (class "Default")
      (node (ref "OK10") (pin "1") (pinfunction "A_1") (pintype "passive"))
      (node (ref "R19") (pin "2") (pinfunction "2_2") (pintype "passive"))
    )
    (net (code "87") (name "Net-(OK10-EMIT)") (class "Default")
      (node (ref "OK10") (pin "3") (pinfunction "EMIT_3") (pintype "passive"))
      (node (ref "R20") (pin "1") (pinfunction "1_1") (pintype "passive"))
    )
    (net (code "88") (name "Net-(OK11-A)") (class "Default")
      (node (ref "OK11") (pin "1") (pinfunction "A_1") (pintype "passive"))
      (node (ref "R21") (pin "2") (pinfunction "2_2") (pintype "passive"))
    )
    (net (code "89") (name "Net-(OK11-EMIT)") (class "Default")
      (node (ref "OK11") (pin "3") (pinfunction "EMIT_3") (pintype "passive"))
      (node (ref "R22") (pin "1") (pinfunction "1_1") (pintype "passive"))
    )
    (net (code "90") (name "Net-(OK12-EMIT)") (class "Default")
      (node (ref "OK12") (pin "3") (pinfunction "EMIT_3") (pintype "passive"))
      (node (ref "R24") (pin "1") (pinfunction "1_1") (pintype "passive"))
    )
    (net (code "91") (name "Net-(OK13-A)") (class "Default")
      (node (ref "OK13") (pin "1") (pinfunction "A_1") (pintype "passive"))
      (node (ref "R25") (pin "2") (pinfunction "2_2") (pintype "passive"))
    )
    (net (code "92") (name "Net-(OK13-EMIT)") (class "Default")
      (node (ref "OK13") (pin "3") (pinfunction "EMIT_3") (pintype "passive"))
      (node (ref "R26") (pin "1") (pinfunction "1_1") (pintype "passive"))
    )
    (net (code "93") (name "Net-(OK14-A)") (class "Default")
      (node (ref "OK14") (pin "1") (pinfunction "A_1") (pintype "passive"))
      (node (ref "R27") (pin "2") (pinfunction "2_2") (pintype "passive"))
    )
    (net (code "94") (name "Net-(OK14-EMIT)") (class "Default")
      (node (ref "OK14") (pin "3") (pinfunction "EMIT_3") (pintype "passive"))
      (node (ref "R28") (pin "1") (pinfunction "1_1") (pintype "passive"))
    )
    (net (code "95") (name "Net-(OK15-A)") (class "Default")
      (node (ref "OK15") (pin "1") (pinfunction "A_1") (pintype "passive"))
      (node (ref "R29") (pin "2") (pinfunction "2_2") (pintype "passive"))
    )
    (net (code "96") (name "Net-(OK15-EMIT)") (class "Default")
      (node (ref "OK15") (pin "3") (pinfunction "EMIT_3") (pintype "passive"))
      (node (ref "R30") (pin "1") (pinfunction "1_1") (pintype "passive"))
    )
    (net (code "97") (name "Net-(OK16-A)") (class "Default")
      (node (ref "OK16") (pin "1") (pinfunction "A_1") (pintype "passive"))
      (node (ref "R31") (pin "2") (pinfunction "2_2") (pintype "passive"))
    )
    (net (code "98") (name "Net-(OK16-EMIT)") (class "Default")
      (node (ref "OK16") (pin "3") (pinfunction "EMIT_3") (pintype "passive"))
      (node (ref "R32") (pin "1") (pinfunction "1_1") (pintype "passive"))
    )
    (net (code "99") (name "Net-(OK17-A)") (class "Default")
      (node (ref "OK17") (pin "1") (pinfunction "A_1") (pintype "passive"))
      (node (ref "R33") (pin "2") (pinfunction "2_2") (pintype "passive"))
    )
    (net (code "100") (name "Net-(OK17-EMIT)") (class "Default")
      (node (ref "OK17") (pin "3") (pinfunction "EMIT_3") (pintype "passive"))
      (node (ref "R34") (pin "1") (pinfunction "1_1") (pintype "passive"))
    )
    (net (code "101") (name "Net-(OK18-A)") (class "Default")
      (node (ref "OK18") (pin "1") (pinfunction "A_1") (pintype "passive"))
      (node (ref "R35") (pin "2") (pinfunction "2_2") (pintype "passive"))
    )
    (net (code "102") (name "Net-(OK18-EMIT)") (class "Default")
      (node (ref "OK18") (pin "3") (pinfunction "EMIT_3") (pintype "passive"))
      (node (ref "R36") (pin "1") (pinfunction "1_1") (pintype "passive"))
    )
    (net (code "103") (name "Net-(T1-B)") (class "Default")
      (node (ref "R2") (pin "2") (pinfunction "2_2") (pintype "passive"))
      (node (ref "T1") (pin "2") (pinfunction "B_2") (pintype "passive"))
    )
    (net (code "104") (name "Net-(T2-B)") (class "Default")
      (node (ref "R4") (pin "2") (pinfunction "2_2") (pintype "passive"))
      (node (ref "T2") (pin "2") (pinfunction "B_2") (pintype "passive"))
    )
    (net (code "105") (name "Net-(T3-B)") (class "Default")
      (node (ref "R6") (pin "2") (pinfunction "2_2") (pintype "passive"))
      (node (ref "T3") (pin "2") (pinfunction "B_2") (pintype "passive"))
    )
    (net (code "106") (name "Net-(T4-B)") (class "Default")
      (node (ref "R8") (pin "2") (pinfunction "2_2") (pintype "passive"))
      (node (ref "T4") (pin "2") (pinfunction "B_2") (pintype "passive"))
    )
    (net (code "107") (name "Net-(T5-B)") (class "Default")
      (node (ref "R10") (pin "2") (pinfunction "2_2") (pintype "passive"))
      (node (ref "T5") (pin "2") (pinfunction "B_2") (pintype "passive"))
    )
    (net (code "108") (name "Net-(T6-B)") (class "Default")
      (node (ref "R12") (pin "2") (pinfunction "2_2") (pintype "passive"))
      (node (ref "T6") (pin "2") (pinfunction "B_2") (pintype "passive"))
    )
    (net (code "109") (name "Net-(T7-B)") (class "Default")
      (node (ref "R14") (pin "2") (pinfunction "2_2") (pintype "passive"))
      (node (ref "T7") (pin "2") (pinfunction "B_2") (pintype "passive"))
    )
    (net (code "110") (name "Net-(T8-B)") (class "Default")
      (node (ref "R16") (pin "2") (pinfunction "2_2") (pintype "passive"))
      (node (ref "T8") (pin "2") (pinfunction "B_2") (pintype "passive"))
    )
    (net (code "111") (name "Net-(T9-B)") (class "Default")
      (node (ref "R18") (pin "2") (pinfunction "2_2") (pintype "passive"))
      (node (ref "T9") (pin "2") (pinfunction "B_2") (pintype "passive"))
    )
    (net (code "112") (name "Net-(T10-B)") (class "Default")
      (node (ref "R20") (pin "2") (pinfunction "2_2") (pintype "passive"))
      (node (ref "T10") (pin "2") (pinfunction "B_2") (pintype "passive"))
    )
    (net (code "113") (name "Net-(T11-B)") (class "Default")
      (node (ref "R22") (pin "2") (pinfunction "2_2") (pintype "passive"))
      (node (ref "T11") (pin "2") (pinfunction "B_2") (pintype "passive"))
    )
    (net (code "114") (name "Net-(T12-B)") (class "Default")
      (node (ref "R24") (pin "2") (pinfunction "2_2") (pintype "passive"))
      (node (ref "T12") (pin "2") (pinfunction "B_2") (pintype "passive"))
    )
    (net (code "115") (name "Net-(T13-B)") (class "Default")
      (node (ref "R26") (pin "2") (pinfunction "2_2") (pintype "passive"))
      (node (ref "T13") (pin "2") (pinfunction "B_2") (pintype "passive"))
    )
    (net (code "116") (name "Net-(T14-B)") (class "Default")
      (node (ref "R28") (pin "2") (pinfunction "2_2") (pintype "passive"))
      (node (ref "T14") (pin "2") (pinfunction "B_2") (pintype "passive"))
    )
    (net (code "117") (name "Net-(T15-B)") (class "Default")
      (node (ref "R30") (pin "2") (pinfunction "2_2") (pintype "passive"))
      (node (ref "T15") (pin "2") (pinfunction "B_2") (pintype "passive"))
    )
    (net (code "118") (name "Net-(T16-B)") (class "Default")
      (node (ref "R32") (pin "2") (pinfunction "2_2") (pintype "passive"))
      (node (ref "T16") (pin "2") (pinfunction "B_2") (pintype "passive"))
    )
    (net (code "119") (name "Net-(T17-B)") (class "Default")
      (node (ref "R34") (pin "2") (pinfunction "2_2") (pintype "passive"))
      (node (ref "T17") (pin "2") (pinfunction "B_2") (pintype "passive"))
    )
    (net (code "120") (name "Net-(T18-B)") (class "Default")
      (node (ref "R36") (pin "2") (pinfunction "2_2") (pintype "passive"))
      (node (ref "T18") (pin "2") (pinfunction "B_2") (pintype "passive"))
    )
    (net (code "121") (name "unconnected-(ICSP-Pad1)") (class "Default")
      (node (ref "ICSP") (pin "1") (pinfunction "1_1") (pintype "passive"))
    )
    (net (code "122") (name "unconnected-(ICSP-Pad2)") (class "Default")
      (node (ref "ICSP") (pin "2") (pinfunction "2_2") (pintype "passive"))
    )
    (net (code "123") (name "unconnected-(ICSP-Pad3)") (class "Default")
      (node (ref "ICSP") (pin "3") (pinfunction "3_3") (pintype "passive"))
    )
    (net (code "124") (name "unconnected-(ICSP-Pad4)") (class "Default")
      (node (ref "ICSP") (pin "4") (pinfunction "4_4") (pintype "passive"))
    )
    (net (code "125") (name "unconnected-(ICSP-Pad5)") (class "Default")
      (node (ref "ICSP") (pin "5") (pinfunction "5_5") (pintype "passive"))
    )
    (net (code "126") (name "unconnected-(ICSP-Pad6)") (class "Default")
      (node (ref "ICSP") (pin "6") (pinfunction "6_6") (pintype "passive"))
    )
    (net (code "127") (name "unconnected-(JP6-Pad1)") (class "Default")
      (node (ref "JP6") (pin "1") (pinfunction "1_1") (pintype "passive"))
    )
    (net (code "128") (name "unconnected-(JP6-Pad2)") (class "Default")
      (node (ref "JP6") (pin "2") (pinfunction "2_2") (pintype "passive"))
    )
    (net (code "129") (name "unconnected-(JP6-Pad3)") (class "Default")
      (node (ref "JP6") (pin "3") (pinfunction "3_3") (pintype "passive"))
    )
    (net (code "130") (name "unconnected-(JP6-Pad4)") (class "Default")
      (node (ref "JP6") (pin "4") (pinfunction "4_4") (pintype "passive"))
    )
    (net (code "131") (name "unconnected-(JP6-Pad8)") (class "Default")
      (node (ref "JP6") (pin "8") (pinfunction "8_8") (pintype "passive"))
    )
    (net (code "132") (name "unconnected-(PWML-Pad2)") (class "Default")
      (node (ref "PWML") (pin "2") (pinfunction "2_2") (pintype "passive"))
    )
  )
)
